# RiskChemi_Monitor_V1_04M1.net
KiCad netlist of a schematic drawn in Altium Designer
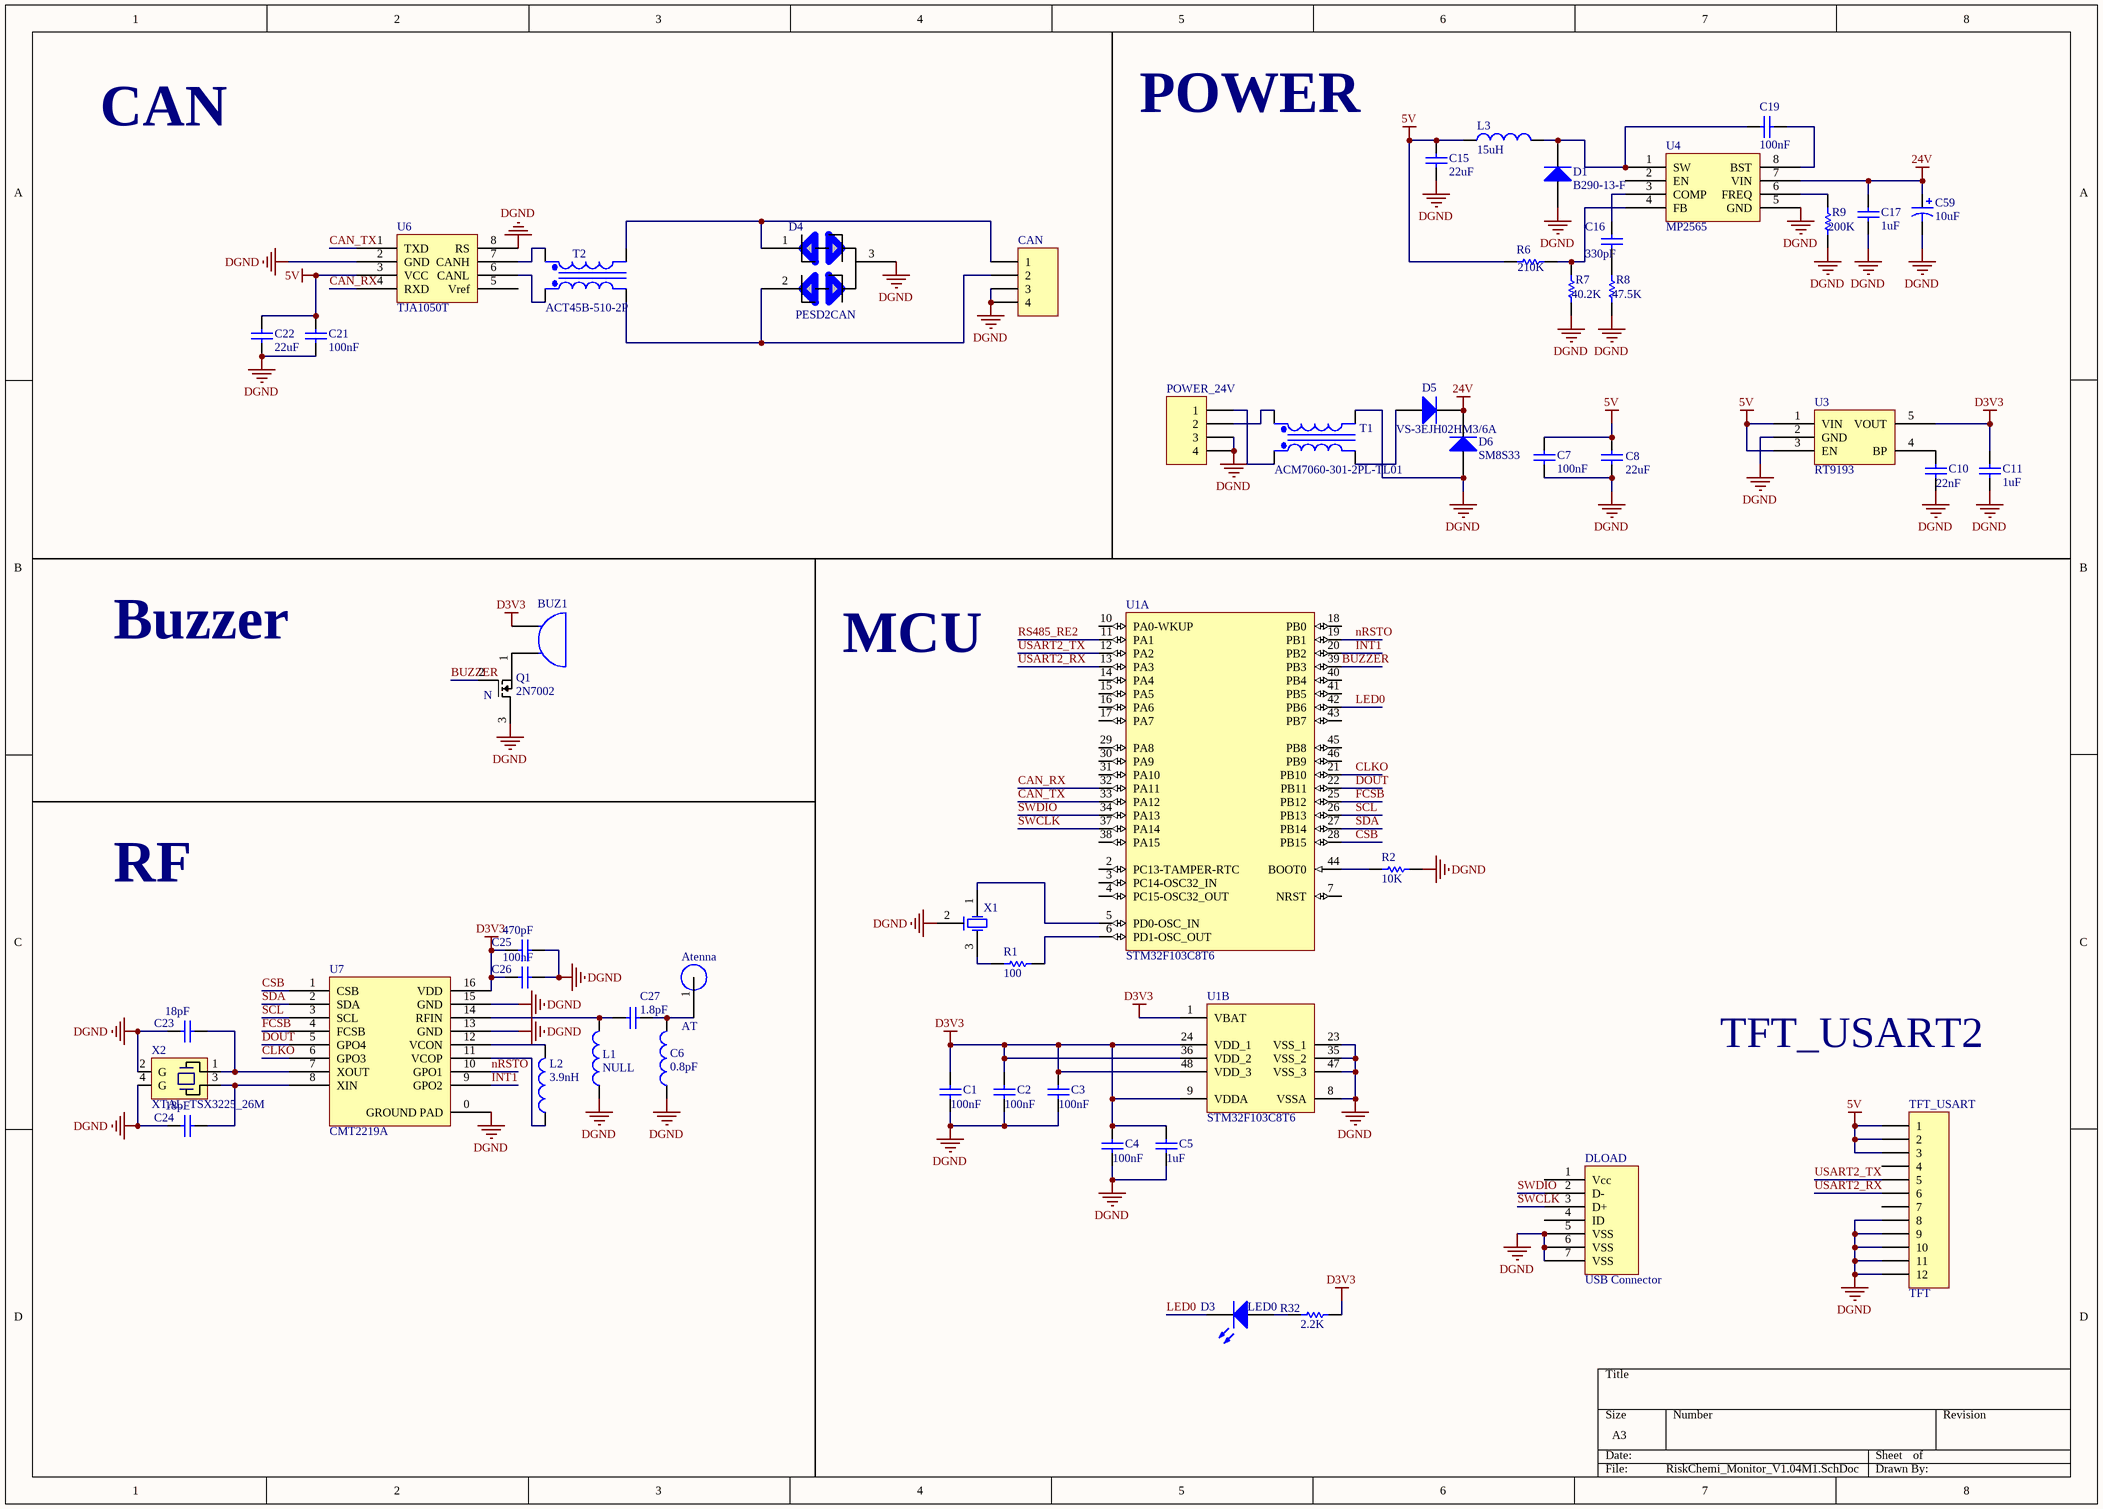
[diagram p0: RiskChemi_Monitor_V1.04M1.SchDoc]

(export (version "E")
  (design (tool "Eeschema 10.0.6"))
  (components
    (comp (ref "Atenna") (value "AT") (footprint "433MHz Atenna") (libsource (lib "MySchlib1") (part "AT")))
    (comp (ref "BUZ1")
      (value "BUZZER")
      (footprint "BUZ0905")
      (description "Buzzer")
      (libsource (lib "杂元件库") (part "BUZZER"))
    )
    (comp (ref "C1")
      (value "100nF")
      (footprint "0603")
      (description "Capacitor")
      (fields (field (name "PUBLISHER") "Altium Limited"))
      (libsource (lib "Miscellaneous Devices") (part "Cap"))
    )
    (comp (ref "C2")
      (value "100nF")
      (footprint "0603")
      (description "Capacitor")
      (fields (field (name "PUBLISHER") "Altium Limited"))
      (libsource (lib "Miscellaneous Devices") (part "Cap"))
    )
    (comp (ref "C3")
      (value "100nF")
      (footprint "0603")
      (description "Capacitor")
      (fields (field (name "PUBLISHER") "Altium Limited"))
      (libsource (lib "Miscellaneous Devices") (part "Cap"))
    )
    (comp (ref "C4")
      (value "100nF")
      (footprint "0603")
      (description "Capacitor")
      (fields (field (name "PUBLISHER") "Altium Limited"))
      (libsource (lib "Miscellaneous Devices") (part "Cap"))
    )
    (comp (ref "C5")
      (value "1uF")
      (footprint "0603")
      (description "Capacitor")
      (fields (field (name "PUBLISHER") "Altium Limited"))
      (libsource (lib "Miscellaneous Devices") (part "Cap"))
    )
    (comp (ref "C6")
      (value "0.8pF")
      (footprint "Miscellaneous Devices:0402")
      (description "Inductor")
      (fields (field (name "PUBLISHER") "Altium Limited"))
      (libsource (lib "Miscellaneous Devices") (part "Inductor"))
    )
    (comp (ref "C7")
      (value "100nF")
      (footprint "0805")
      (description "Capacitor,100V")
      (fields (field (name "PUBLISHER") "Altium Limited"))
      (libsource (lib "Miscellaneous Devices") (part "Cap"))
    )
    (comp (ref "C8")
      (value "22uF")
      (footprint "0805")
      (description "Capacitor")
      (fields (field (name "PUBLISHER") "Altium Limited"))
      (libsource (lib "Miscellaneous Devices") (part "Cap"))
    )
    (comp (ref "C10")
      (value "22nF")
      (footprint "BinFeng:0603")
      (description "Capacitor")
      (fields (field (name "PUBLISHER") "Altium Limited"))
      (libsource (lib "Miscellaneous Devices") (part "Cap"))
    )
    (comp (ref "C11")
      (value "1uF")
      (footprint "BinFeng:0603")
      (description "Capacitor")
      (fields (field (name "PUBLISHER") "Altium Limited"))
      (libsource (lib "Miscellaneous Devices") (part "Cap"))
    )
    (comp (ref "C15")
      (value "22uF")
      (footprint "0805")
      (description "Capacitor,50V")
      (fields (field (name "PUBLISHER") "Altium Limited"))
      (libsource (lib "Miscellaneous Devices") (part "Cap"))
    )
    (comp (ref "C16")
      (value "330pF")
      (footprint "BinFeng:0402")
      (description "Capacitor")
      (fields (field (name "PUBLISHER") "Altium Limited"))
      (libsource (lib "Miscellaneous Devices") (part "Cap"))
    )
    (comp (ref "C17")
      (value "1uF")
      (footprint "0805")
      (description "Capacitor,100V")
      (fields (field (name "PUBLISHER") "Altium Limited"))
      (libsource (lib "Miscellaneous Devices") (part "Cap"))
    )
    (comp (ref "C19")
      (value "100nF")
      (footprint "BinFeng:0402")
      (description "Capacitor")
      (fields (field (name "PUBLISHER") "Altium Limited"))
      (libsource (lib "Miscellaneous Devices") (part "Cap"))
    )
    (comp (ref "C21")
      (value "100nF")
      (footprint "0603")
      (description "Capacitor")
      (fields (field (name "PUBLISHER") "Altium Limited"))
      (libsource (lib "Miscellaneous Devices") (part "Cap"))
    )
    (comp (ref "C22")
      (value "22uF")
      (footprint "0805")
      (description "Capacitor")
      (fields (field (name "PUBLISHER") "Altium Limited"))
      (libsource (lib "Miscellaneous Devices") (part "Cap"))
    )
    (comp (ref "C23")
      (value "18pF")
      (footprint "BinFeng:0402")
      (description "Capacitor")
      (fields (field (name "PUBLISHER") "Altium Limited"))
      (libsource (lib "Miscellaneous Devices") (part "Cap"))
    )
    (comp (ref "C24")
      (value "18pF")
      (footprint "BinFeng:0402")
      (description "Capacitor")
      (fields (field (name "PUBLISHER") "Altium Limited"))
      (libsource (lib "Miscellaneous Devices") (part "Cap"))
    )
    (comp (ref "C25")
      (value "470pF")
      (footprint "BinFeng:0402")
      (description "Capacitor")
      (fields (field (name "PUBLISHER") "Altium Limited"))
      (libsource (lib "Miscellaneous Devices") (part "Cap"))
    )
    (comp (ref "C26")
      (value "100nF")
      (footprint "BinFeng:0603")
      (description "Capacitor")
      (fields (field (name "PUBLISHER") "Altium Limited"))
      (libsource (lib "Miscellaneous Devices") (part "Cap"))
    )
    (comp (ref "C27")
      (value "1.8pF")
      (footprint "BinFeng:nosilk_0402")
      (description "Capacitor")
      (fields (field (name "PUBLISHER") "Altium Limited"))
      (libsource (lib "Miscellaneous Devices") (part "Cap"))
    )
    (comp (ref "C59")
      (value "10uF")
      (footprint "6032_pol")
      (description "Polarized Capacitor (Radial)")
      (fields (field (name "PUBLISHER") "Altium Limited"))
      (libsource (lib "Miscellaneous Devices") (part "Cap Pol1"))
    )
    (comp (ref "CAN")
      (value "Header 4")
      (footprint "C3000VS")
      (description "Header, 4-Pin")
      (fields (field (name "PUBLISHER") "Altium Limited"))
      (libsource (lib "") (part "Header 4_1"))
    )
    (comp (ref "D1")
      (value "B290-13-F")
      (footprint "back:B290")
      (description "Default Diode")
      (fields (field (name "PUBLISHER") "Altium Limited"))
      (libsource (lib "Miscellaneous Devices") (part "Diode"))
    )
    (comp (ref "D3")
      (value "LED0")
      (footprint "LED")
      (description "green LED")
      (fields (field (name "PUBLISHER") "Altium Limited"))
      (libsource (lib "Miscellaneous Devices") (part "LED0"))
    )
    (comp (ref "D4")
      (value "PESD2CAN")
      (footprint "SOT23")
      (libsource (lib "BinFeng_Connectors") (part "PESD1CAN"))
    )
    (comp (ref "D5")
      (value "VS-3EJH02HM3/6A")
      (footprint "back:B290")
      (description "1 Amp General Purpose Rectifier")
      (fields (field (name "PUBLISHER") "Altium Limited"))
      (libsource (lib "Miscellaneous Devices") (part "Diode 1N4007"))
    )
    (comp (ref "D6")
      (value "SM8S33")
      (footprint "SM8S")
      (description "1 Amp General Purpose Rectifier")
      (fields (field (name "PUBLISHER") "Altium Limited"))
      (libsource (lib "Miscellaneous Devices") (part "Diode 1N4007"))
    )
    (comp (ref "DLOAD")
      (value "USB Connector")
      (footprint "Mini_USB")
      (libsource (lib "BinFeng_Connectors") (part "Component_1"))
    )
    (comp (ref "L1")
      (value "NULL")
      (footprint "Miscellaneous Devices:0402")
      (description "Inductor")
      (fields (field (name "PUBLISHER") "Altium Limited"))
      (libsource (lib "Miscellaneous Devices") (part "Inductor"))
    )
    (comp (ref "L2")
      (value "3.9nH")
      (footprint "BinFeng:0603")
      (description "Inductor")
      (fields (field (name "PUBLISHER") "Altium Limited"))
      (libsource (lib "Miscellaneous Devices") (part "Inductor"))
    )
    (comp (ref "L3")
      (value "15uH")
      (footprint "4*4 Inductor")
      (description "Inductor, 1A")
      (fields (field (name "PUBLISHER") "Altium Limited"))
      (libsource (lib "Miscellaneous Devices") (part "Inductor"))
    )
    (comp (ref "POWER_24V")
      (value "Header 4")
      (footprint "C3000VS")
      (description "Header, 4-Pin")
      (fields (field (name "PUBLISHER") "Altium Limited"))
      (libsource (lib "Miscellaneous Connectors") (part "Header 4"))
    )
    (comp (ref "Q1") (value "2N7002") (footprint "2N7002") (libsource (lib "seeder") (part "N-MOSFET")))
    (comp (ref "R1")
      (value "100")
      (footprint "back:0603")
      (description "Resistor")
      (fields (field (name "PUBLISHER") "Altium Limited"))
      (libsource (lib "Miscellaneous Devices") (part "Res1"))
    )
    (comp (ref "R2")
      (value "10K")
      (footprint "back:0603")
      (description "Resistor")
      (fields (field (name "PUBLISHER") "Altium Limited"))
      (libsource (lib "Miscellaneous Devices") (part "Res1"))
    )
    (comp (ref "R6")
      (value "210K")
      (footprint "BinFeng:0402")
      (description "Resistor")
      (fields (field (name "PUBLISHER") "Altium Limited"))
      (libsource (lib "Miscellaneous Devices") (part "Res1"))
    )
    (comp (ref "R7")
      (value "40.2K")
      (footprint "BinFeng:0402")
      (description "Resistor")
      (fields (field (name "PUBLISHER") "Altium Limited"))
      (libsource (lib "Miscellaneous Devices") (part "Res1"))
    )
    (comp (ref "R8")
      (value "47.5K")
      (footprint "BinFeng:0402")
      (description "Resistor")
      (fields (field (name "PUBLISHER") "Altium Limited"))
      (libsource (lib "Miscellaneous Devices") (part "Res1"))
    )
    (comp (ref "R9")
      (value "200K")
      (footprint "BinFeng:0402")
      (description "Resistor")
      (fields (field (name "PUBLISHER") "Altium Limited"))
      (libsource (lib "Miscellaneous Devices") (part "Res1"))
    )
    (comp (ref "R32")
      (value "2.2K")
      (footprint "BinFeng:0603")
      (description "Resistor")
      (fields (field (name "PUBLISHER") "Altium Limited"))
      (libsource (lib "Miscellaneous Devices") (part "Res1"))
    )
    (comp (ref "T1")
      (value "ACM7060-301-2PL-TL01")
      (footprint "ACM7060-301-2P-TL01")
      (description "Transformer (Equivalent Circuit Model)")
      (fields (field (name "PUBLISHER") "Altium Limited"))
      (libsource (lib "Miscellaneous Devices") (part "Trans Eq"))
    )
    (comp (ref "T2")
      (value "ACT45B-510-2P")
      (footprint "ACT45B-510-2P")
      (description "Transformer (Equivalent Circuit Model)")
      (fields (field (name "PUBLISHER") "Altium Limited"))
      (libsource (lib "Miscellaneous Devices") (part "Trans Eq"))
    )
    (comp (ref "TFT_USART")
      (value "TFT")
      (footprint "FCC_10pin_1mm")
      (description "Header, 12-Pin")
      (fields (field (name "PUBLISHER") "Altium Limited"))
      (libsource (lib "Miscellaneous Connectors") (part "Header 12"))
    )
    (comp (ref "U1")
      (value "STM32F103C8T6")
      (footprint "STM-LQFP48_N")
      (libsource (lib "STMicroelectronics STM32 F1") (part "STM32F103C8T6"))
    )
    (comp (ref "U3") (value "RT9193") (footprint "SOT-23-5") (libsource (lib "BinFeng_IC") (part "RT9193")))
    (comp (ref "U4")
      (value "MP2565")
      (footprint "SO8")
      (description "DCDC 4.5V~28V input 1.8V ~5V output low power")
      (libsource (lib "BinFeng_IC") (part "MP1584"))
    )
    (comp (ref "U6")
      (value "TJA1050T")
      (footprint "SO8")
      (description "CAN Tranceiver")
      (libsource (lib "BinFeng_IC") (part "TJA1050T"))
    )
    (comp (ref "U7")
      (value "CMT2219A")
      (footprint "back:QFN16")
      (libsource (lib "BinFeng_IC") (part "CMT2219A"))
    )
    (comp (ref "X1") (value "8M smd") (footprint "8Mhz_XTAL") (libsource (lib "Schlib1") (part "8M smd")))
    (comp (ref "X2")
      (value "XTAL_TSX3225_26M")
      (footprint "XTAL3225")
      (libsource (lib "BinFeng_IC") (part "XTAL_Negative"))
    )
  )
  (nets
    (net (code "1") (name "/BUZZER") (class "Default")
      (node (ref "Q1") (pin "2") (pinfunction "G_2") (pintype "passive"))
      (node (ref "U1") (pin "39") (pinfunction "PB3_39") (pintype "bidirectional"))
    )
    (net (code "2") (name "/CAN_RX") (class "Default")
      (node (ref "U1") (pin "32") (pinfunction "PA11_32") (pintype "bidirectional"))
      (node (ref "U6") (pin "4") (pinfunction "RXD_4") (pintype "passive"))
    )
    (net (code "3") (name "/CAN_TX") (class "Default")
      (node (ref "U1") (pin "33") (pinfunction "PA12_33") (pintype "bidirectional"))
      (node (ref "U6") (pin "1") (pinfunction "TXD_1") (pintype "passive"))
    )
    (net (code "4") (name "/CLKO") (class "Default")
      (node (ref "U1") (pin "21") (pinfunction "PB10_21") (pintype "bidirectional"))
      (node (ref "U7") (pin "6") (pinfunction "GPO3_6") (pintype "passive"))
    )
    (net (code "5") (name "/CSB") (class "Default")
      (node (ref "U1") (pin "28") (pinfunction "PB15_28") (pintype "bidirectional"))
      (node (ref "U7") (pin "1") (pinfunction "CSB_1") (pintype "passive"))
    )
    (net (code "6") (name "/DOUT") (class "Default")
      (node (ref "U1") (pin "22") (pinfunction "PB11_22") (pintype "bidirectional"))
      (node (ref "U7") (pin "5") (pinfunction "GPO4_5") (pintype "passive"))
    )
    (net (code "7") (name "/FCSB") (class "Default")
      (node (ref "U1") (pin "25") (pinfunction "PB12_25") (pintype "bidirectional"))
      (node (ref "U7") (pin "4") (pinfunction "FCSB_4") (pintype "passive"))
    )
    (net (code "8") (name "/INT1") (class "Default")
      (node (ref "U1") (pin "20") (pinfunction "PB2_20") (pintype "bidirectional"))
      (node (ref "U7") (pin "9") (pinfunction "GPO2_9") (pintype "passive"))
    )
    (net (code "9") (name "/LED0") (class "Default")
      (node (ref "D3") (pin "2") (pinfunction "K_2") (pintype "passive"))
      (node (ref "U1") (pin "42") (pinfunction "PB6_42") (pintype "bidirectional"))
    )
    (net (code "10") (name "/RS485_RE2") (class "Default")
      (node (ref "U1") (pin "11") (pinfunction "PA1_11") (pintype "bidirectional"))
    )
    (net (code "11") (name "/SCL") (class "Default")
      (node (ref "U1") (pin "26") (pinfunction "PB13_26") (pintype "bidirectional"))
      (node (ref "U7") (pin "3") (pinfunction "SCL_3") (pintype "passive"))
    )
    (net (code "12") (name "/SDA") (class "Default")
      (node (ref "U1") (pin "27") (pinfunction "PB14_27") (pintype "bidirectional"))
      (node (ref "U7") (pin "2") (pinfunction "SDA_2") (pintype "passive"))
    )
    (net (code "13") (name "/SWCLK") (class "Default")
      (node (ref "DLOAD") (pin "3") (pinfunction "D+_3") (pintype "passive"))
      (node (ref "U1") (pin "37") (pinfunction "PA14_37") (pintype "bidirectional"))
    )
    (net (code "14") (name "/SWDIO") (class "Default")
      (node (ref "DLOAD") (pin "2") (pinfunction "D-_2") (pintype "passive"))
      (node (ref "U1") (pin "34") (pinfunction "PA13_34") (pintype "bidirectional"))
    )
    (net (code "15") (name "/USART2_RX") (class "Default")
      (node (ref "TFT_USART") (pin "6") (pinfunction "6_6") (pintype "passive"))
      (node (ref "U1") (pin "13") (pinfunction "PA3_13") (pintype "bidirectional"))
    )
    (net (code "16") (name "/USART2_TX") (class "Default")
      (node (ref "TFT_USART") (pin "5") (pinfunction "5_5") (pintype "passive"))
      (node (ref "U1") (pin "12") (pinfunction "PA2_12") (pintype "bidirectional"))
    )
    (net (code "17") (name "/nRSTO") (class "Default")
      (node (ref "U1") (pin "19") (pinfunction "PB1_19") (pintype "bidirectional"))
      (node (ref "U7") (pin "10") (pinfunction "GPO1_10") (pintype "passive"))
    )
    (net (code "18") (name "5V") (class "Default")
      (node (ref "C15") (pin "2") (pinfunction "2_2") (pintype "passive"))
      (node (ref "C21") (pin "1") (pinfunction "1_1") (pintype "passive"))
      (node (ref "C22") (pin "2") (pinfunction "2_2") (pintype "passive"))
      (node (ref "C7") (pin "2") (pinfunction "2_2") (pintype "passive"))
      (node (ref "C8") (pin "2") (pinfunction "2_2") (pintype "passive"))
      (node (ref "L3") (pin "1") (pinfunction "1_1") (pintype "passive"))
      (node (ref "R6") (pin "2") (pinfunction "2_2") (pintype "passive"))
      (node (ref "TFT_USART") (pin "1") (pinfunction "1_1") (pintype "passive"))
      (node (ref "TFT_USART") (pin "2") (pinfunction "2_2") (pintype "passive"))
      (node (ref "TFT_USART") (pin "3") (pinfunction "3_3") (pintype "passive"))
      (node (ref "U3") (pin "1") (pinfunction "VIN_1") (pintype "passive"))
      (node (ref "U3") (pin "3") (pinfunction "EN_3") (pintype "passive"))
      (node (ref "U6") (pin "3") (pinfunction "VCC_3") (pintype "passive"))
    )
    (net (code "19") (name "24V") (class "Default")
      (node (ref "C17") (pin "2") (pinfunction "2_2") (pintype "passive"))
      (node (ref "C59") (pin "1") (pinfunction "1_1") (pintype "passive"))
      (node (ref "D5") (pin "2") (pinfunction "K_2") (pintype "passive"))
      (node (ref "D6") (pin "2") (pinfunction "K_2") (pintype "passive"))
      (node (ref "U4") (pin "7") (pinfunction "VIN_7") (pintype "passive"))
    )
    (net (code "20") (name "D3V3") (class "Default")
      (node (ref "BUZ1") (pin "1") (pinfunction "A_1") (pintype "passive"))
      (node (ref "C1") (pin "2") (pinfunction "2_2") (pintype "passive"))
      (node (ref "C11") (pin "2") (pinfunction "2_2") (pintype "passive"))
      (node (ref "C2") (pin "2") (pinfunction "2_2") (pintype "passive"))
      (node (ref "C25") (pin "2") (pinfunction "2_2") (pintype "passive"))
      (node (ref "C26") (pin "2") (pinfunction "2_2") (pintype "passive"))
      (node (ref "C3") (pin "2") (pinfunction "2_2") (pintype "passive"))
      (node (ref "C4") (pin "2") (pinfunction "2_2") (pintype "passive"))
      (node (ref "C5") (pin "2") (pinfunction "2_2") (pintype "passive"))
      (node (ref "R32") (pin "1") (pinfunction "1_1") (pintype "passive"))
      (node (ref "U1") (pin "1") (pinfunction "VBAT_1") (pintype "power_in"))
      (node (ref "U1") (pin "24") (pinfunction "VDD_1_24") (pintype "power_in"))
      (node (ref "U1") (pin "36") (pinfunction "VDD_2_36") (pintype "power_in"))
      (node (ref "U1") (pin "48") (pinfunction "VDD_3_48") (pintype "power_in"))
      (node (ref "U1") (pin "9") (pinfunction "VDDA_9") (pintype "power_in"))
      (node (ref "U3") (pin "5") (pinfunction "VOUT_5") (pintype "passive"))
      (node (ref "U7") (pin "16") (pinfunction "VDD_16") (pintype "passive"))
    )
    (net (code "21") (name "DGND") (class "Default")
      (node (ref "C1") (pin "1") (pinfunction "1_1") (pintype "passive"))
      (node (ref "C10") (pin "1") (pinfunction "1_1") (pintype "passive"))
      (node (ref "C11") (pin "1") (pinfunction "1_1") (pintype "passive"))
      (node (ref "C15") (pin "1") (pinfunction "1_1") (pintype "passive"))
      (node (ref "C17") (pin "1") (pinfunction "1_1") (pintype "passive"))
      (node (ref "C2") (pin "1") (pinfunction "1_1") (pintype "passive"))
      (node (ref "C21") (pin "2") (pinfunction "2_2") (pintype "passive"))
      (node (ref "C22") (pin "1") (pinfunction "1_1") (pintype "passive"))
      (node (ref "C23") (pin "2") (pinfunction "2_2") (pintype "passive"))
      (node (ref "C24") (pin "2") (pinfunction "2_2") (pintype "passive"))
      (node (ref "C25") (pin "1") (pinfunction "1_1") (pintype "passive"))
      (node (ref "C26") (pin "1") (pinfunction "1_1") (pintype "passive"))
      (node (ref "C3") (pin "1") (pinfunction "1_1") (pintype "passive"))
      (node (ref "C4") (pin "1") (pinfunction "1_1") (pintype "passive"))
      (node (ref "C5") (pin "1") (pinfunction "1_1") (pintype "passive"))
      (node (ref "C59") (pin "2") (pinfunction "2_2") (pintype "passive"))
      (node (ref "C6") (pin "1") (pinfunction "1_1") (pintype "passive"))
      (node (ref "C7") (pin "1") (pinfunction "1_1") (pintype "passive"))
      (node (ref "C8") (pin "1") (pinfunction "1_1") (pintype "passive"))
      (node (ref "CAN") (pin "3") (pinfunction "3_3") (pintype "passive"))
      (node (ref "CAN") (pin "4") (pinfunction "4_4") (pintype "passive"))
      (node (ref "D1") (pin "1") (pinfunction "A_1") (pintype "passive"))
      (node (ref "D4") (pin "3") (pinfunction "13_3") (pintype "passive"))
      (node (ref "D6") (pin "1") (pinfunction "A_1") (pintype "passive"))
      (node (ref "DLOAD") (pin "5") (pinfunction "VSS_5") (pintype "passive"))
      (node (ref "DLOAD") (pin "6") (pinfunction "VSS_6") (pintype "passive"))
      (node (ref "DLOAD") (pin "7") (pinfunction "VSS_7") (pintype "passive"))
      (node (ref "L1") (pin "1") (pinfunction "1_1") (pintype "passive"))
      (node (ref "POWER_24V") (pin "3") (pinfunction "3_3") (pintype "passive"))
      (node (ref "POWER_24V") (pin "4") (pinfunction "4_4") (pintype "passive"))
      (node (ref "Q1") (pin "3") (pinfunction "S_3") (pintype "passive"))
      (node (ref "R2") (pin "2") (pinfunction "2_2") (pintype "passive"))
      (node (ref "R7") (pin "1") (pinfunction "1_1") (pintype "passive"))
      (node (ref "R8") (pin "1") (pinfunction "1_1") (pintype "passive"))
      (node (ref "R9") (pin "1") (pinfunction "1_1") (pintype "passive"))
      (node (ref "T1") (pin "4") (pinfunction "Sec-_4") (pintype "passive"))
      (node (ref "TFT_USART") (pin "10") (pinfunction "10_10") (pintype "passive"))
      (node (ref "TFT_USART") (pin "11") (pinfunction "11_11") (pintype "passive"))
      (node (ref "TFT_USART") (pin "12") (pinfunction "12_12") (pintype "passive"))
      (node (ref "TFT_USART") (pin "8") (pinfunction "8_8") (pintype "passive"))
      (node (ref "TFT_USART") (pin "9") (pinfunction "9_9") (pintype "passive"))
      (node (ref "U1") (pin "23") (pinfunction "VSS_1_23") (pintype "power_in"))
      (node (ref "U1") (pin "35") (pinfunction "VSS_2_35") (pintype "power_in"))
      (node (ref "U1") (pin "47") (pinfunction "VSS_3_47") (pintype "power_in"))
      (node (ref "U1") (pin "8") (pinfunction "VSSA_8") (pintype "power_in"))
      (node (ref "U3") (pin "2") (pinfunction "GND_2") (pintype "passive"))
      (node (ref "U4") (pin "5") (pinfunction "GND_5") (pintype "passive"))
      (node (ref "U6") (pin "2") (pinfunction "GND_2") (pintype "passive"))
      (node (ref "U6") (pin "8") (pinfunction "RS_8") (pintype "passive"))
      (node (ref "U7") (pin "0") (pinfunction "GROUND_PAD_0") (pintype "passive"))
      (node (ref "U7") (pin "13") (pinfunction "GND_13") (pintype "passive"))
      (node (ref "U7") (pin "15") (pinfunction "GND_15") (pintype "passive"))
      (node (ref "X1") (pin "2") (pinfunction "GND_2") (pintype "passive"))
      (node (ref "X2") (pin "2") (pinfunction "G_2") (pintype "passive"))
      (node (ref "X2") (pin "4") (pinfunction "G_4") (pintype "passive"))
    )
    (net (code "22") (name "Net-(Atenna-Pad1)") (class "Default")
      (node (ref "Atenna") (pin "1") (pinfunction "1_1") (pintype "passive"))
      (node (ref "C27") (pin "1") (pinfunction "1_1") (pintype "passive"))
      (node (ref "C6") (pin "2") (pinfunction "2_2") (pintype "passive"))
    )
    (net (code "23") (name "Net-(BUZ1-B)") (class "Default")
      (node (ref "BUZ1") (pin "2") (pinfunction "B_2") (pintype "passive"))
      (node (ref "Q1") (pin "1") (pinfunction "D_1") (pintype "passive"))
    )
    (net (code "24") (name "Net-(C16-Pad2)") (class "Default")
      (node (ref "C16") (pin "2") (pinfunction "2_2") (pintype "passive"))
      (node (ref "R8") (pin "2") (pinfunction "2_2") (pintype "passive"))
    )
    (net (code "25") (name "Net-(D1-K)") (class "Default")
      (node (ref "C19") (pin "2") (pinfunction "2_2") (pintype "passive"))
      (node (ref "D1") (pin "2") (pinfunction "K_2") (pintype "passive"))
      (node (ref "L3") (pin "2") (pinfunction "2_2") (pintype "passive"))
      (node (ref "U4") (pin "1") (pinfunction "SW_1") (pintype "passive"))
    )
    (net (code "26") (name "Net-(D3-A)") (class "Default")
      (node (ref "D3") (pin "1") (pinfunction "A_1") (pintype "passive"))
      (node (ref "R32") (pin "2") (pinfunction "2_2") (pintype "passive"))
    )
    (net (code "27") (name "Net-(D4-11)") (class "Default")
      (node (ref "CAN") (pin "1") (pinfunction "1_1") (pintype "passive"))
      (node (ref "D4") (pin "1") (pinfunction "11_1") (pintype "passive"))
      (node (ref "T2") (pin "4") (pinfunction "Sec-_4") (pintype "passive"))
    )
    (net (code "28") (name "Net-(D4-12)") (class "Default")
      (node (ref "CAN") (pin "2") (pinfunction "2_2") (pintype "passive"))
      (node (ref "D4") (pin "2") (pinfunction "12_2") (pintype "passive"))
      (node (ref "T2") (pin "2") (pinfunction "Pri-_2") (pintype "passive"))
    )
    (net (code "29") (name "Net-(D5-A)") (class "Default")
      (node (ref "D5") (pin "1") (pinfunction "A_1") (pintype "passive"))
      (node (ref "T1") (pin "2") (pinfunction "Pri-_2") (pintype "passive"))
    )
    (net (code "30") (name "Net-(T1-Pri+)") (class "Default")
      (node (ref "POWER_24V") (pin "1") (pinfunction "1_1") (pintype "passive"))
      (node (ref "T1") (pin "1") (pinfunction "Pri+_1") (pintype "passive"))
    )
    (net (code "31") (name "Net-(T1-Sec+)") (class "Default")
      (node (ref "POWER_24V") (pin "2") (pinfunction "2_2") (pintype "passive"))
      (node (ref "T1") (pin "3") (pinfunction "Sec+_3") (pintype "passive"))
    )
    (net (code "32") (name "Net-(T2-Pri+)") (class "Default")
      (node (ref "T2") (pin "1") (pinfunction "Pri+_1") (pintype "passive"))
      (node (ref "U6") (pin "6") (pinfunction "CANL_6") (pintype "passive"))
    )
    (net (code "33") (name "Net-(T2-Sec+)") (class "Default")
      (node (ref "T2") (pin "3") (pinfunction "Sec+_3") (pintype "passive"))
      (node (ref "U6") (pin "7") (pinfunction "CANH_7") (pintype "passive"))
    )
    (net (code "34") (name "Net-(U1A-BOOT0)") (class "Default")
      (node (ref "R2") (pin "1") (pinfunction "1_1") (pintype "passive"))
      (node (ref "U1") (pin "44") (pinfunction "BOOT0_44") (pintype "input"))
    )
    (net (code "35") (name "Net-(U1A-PD0-OSC_IN)") (class "Default")
      (node (ref "U1") (pin "5") (pinfunction "PD0-OSC_IN_5") (pintype "bidirectional"))
      (node (ref "X1") (pin "1") (pinfunction "OSC1_1") (pintype "passive"))
    )
    (net (code "36") (name "Net-(U1A-PD1-OSC_OUT)") (class "Default")
      (node (ref "R1") (pin "2") (pinfunction "2_2") (pintype "passive"))
      (node (ref "U1") (pin "6") (pinfunction "PD1-OSC_OUT_6") (pintype "bidirectional"))
    )
    (net (code "37") (name "Net-(U3-BP)") (class "Default")
      (node (ref "C10") (pin "2") (pinfunction "2_2") (pintype "passive"))
      (node (ref "U3") (pin "4") (pinfunction "BP_4") (pintype "passive"))
    )
    (net (code "38") (name "Net-(U4-BST)") (class "Default")
      (node (ref "C19") (pin "1") (pinfunction "1_1") (pintype "passive"))
      (node (ref "U4") (pin "8") (pinfunction "BST_8") (pintype "passive"))
    )
    (net (code "39") (name "Net-(U4-COMP)") (class "Default")
      (node (ref "C16") (pin "1") (pinfunction "1_1") (pintype "passive"))
      (node (ref "U4") (pin "3") (pinfunction "COMP_3") (pintype "passive"))
    )
    (net (code "40") (name "Net-(U4-FB)") (class "Default")
      (node (ref "R6") (pin "1") (pinfunction "1_1") (pintype "passive"))
      (node (ref "R7") (pin "2") (pinfunction "2_2") (pintype "passive"))
      (node (ref "U4") (pin "4") (pinfunction "FB_4") (pintype "passive"))
    )
    (net (code "41") (name "Net-(U4-FREQ)") (class "Default")
      (node (ref "R9") (pin "2") (pinfunction "2_2") (pintype "passive"))
      (node (ref "U4") (pin "6") (pinfunction "FREQ_6") (pintype "passive"))
    )
    (net (code "42") (name "Net-(U7-RFIN)") (class "Default")
      (node (ref "C27") (pin "2") (pinfunction "2_2") (pintype "passive"))
      (node (ref "L1") (pin "2") (pinfunction "2_2") (pintype "passive"))
      (node (ref "U7") (pin "14") (pinfunction "RFIN_14") (pintype "passive"))
    )
    (net (code "43") (name "Net-(U7-VCON)") (class "Default")
      (node (ref "L2") (pin "2") (pinfunction "2_2") (pintype "passive"))
      (node (ref "U7") (pin "12") (pinfunction "VCON_12") (pintype "passive"))
    )
    (net (code "44") (name "Net-(U7-VCOP)") (class "Default")
      (node (ref "L2") (pin "1") (pinfunction "1_1") (pintype "passive"))
      (node (ref "U7") (pin "11") (pinfunction "VCOP_11") (pintype "passive"))
    )
    (net (code "45") (name "Net-(U7-XIN)") (class "Default")
      (node (ref "C24") (pin "1") (pinfunction "1_1") (pintype "passive"))
      (node (ref "U7") (pin "8") (pinfunction "XIN_8") (pintype "passive"))
      (node (ref "X2") (pin "3") (pintype "passive"))
    )
    (net (code "46") (name "Net-(U7-XOUT)") (class "Default")
      (node (ref "C23") (pin "1") (pinfunction "1_1") (pintype "passive"))
      (node (ref "U7") (pin "7") (pinfunction "XOUT_7") (pintype "passive"))
      (node (ref "X2") (pin "1") (pintype "passive"))
    )
    (net (code "47") (name "Net-(X1-OSC2)") (class "Default")
      (node (ref "R1") (pin "1") (pinfunction "1_1") (pintype "passive"))
      (node (ref "X1") (pin "3") (pinfunction "OSC2_3") (pintype "passive"))
    )
    (net (code "48") (name "unconnected-(DLOAD-ID-Pad4)") (class "Default")
      (node (ref "DLOAD") (pin "4") (pinfunction "ID_4") (pintype "passive"))
    )
    (net (code "49") (name "unconnected-(DLOAD-Vcc-Pad1)") (class "Default")
      (node (ref "DLOAD") (pin "1") (pinfunction "Vcc_1") (pintype "passive"))
    )
    (net (code "50") (name "unconnected-(TFT_USART-Pad4)") (class "Default")
      (node (ref "TFT_USART") (pin "4") (pinfunction "4_4") (pintype "passive"))
    )
    (net (code "51") (name "unconnected-(TFT_USART-Pad7)") (class "Default")
      (node (ref "TFT_USART") (pin "7") (pinfunction "7_7") (pintype "passive"))
    )
    (net (code "52") (name "unconnected-(U1A-NRST-Pad7)") (class "Default")
      (node (ref "U1") (pin "7") (pinfunction "NRST_7") (pintype "bidirectional"))
    )
    (net (code "53") (name "unconnected-(U1A-PA0-WKUP-Pad10)") (class "Default")
      (node (ref "U1") (pin "10") (pinfunction "PA0-WKUP_10") (pintype "bidirectional"))
    )
    (net (code "54") (name "unconnected-(U1A-PA4-Pad14)") (class "Default")
      (node (ref "U1") (pin "14") (pinfunction "PA4_14") (pintype "bidirectional"))
    )
    (net (code "55") (name "unconnected-(U1A-PA5-Pad15)") (class "Default")
      (node (ref "U1") (pin "15") (pinfunction "PA5_15") (pintype "bidirectional"))
    )
    (net (code "56") (name "unconnected-(U1A-PA6-Pad16)") (class "Default")
      (node (ref "U1") (pin "16") (pinfunction "PA6_16") (pintype "bidirectional"))
    )
    (net (code "57") (name "unconnected-(U1A-PA7-Pad17)") (class "Default")
      (node (ref "U1") (pin "17") (pinfunction "PA7_17") (pintype "bidirectional"))
    )
    (net (code "58") (name "unconnected-(U1A-PA8-Pad29)") (class "Default")
      (node (ref "U1") (pin "29") (pinfunction "PA8_29") (pintype "bidirectional"))
    )
    (net (code "59") (name "unconnected-(U1A-PA9-Pad30)") (class "Default")
      (node (ref "U1") (pin "30") (pinfunction "PA9_30") (pintype "bidirectional"))
    )
    (net (code "60") (name "unconnected-(U1A-PA10-Pad31)") (class "Default")
      (node (ref "U1") (pin "31") (pinfunction "PA10_31") (pintype "bidirectional"))
    )
    (net (code "61") (name "unconnected-(U1A-PA15-Pad38)") (class "Default")
      (node (ref "U1") (pin "38") (pinfunction "PA15_38") (pintype "bidirectional"))
    )
    (net (code "62") (name "unconnected-(U1A-PB0-Pad18)") (class "Default")
      (node (ref "U1") (pin "18") (pinfunction "PB0_18") (pintype "bidirectional"))
    )
    (net (code "63") (name "unconnected-(U1A-PB4-Pad40)") (class "Default")
      (node (ref "U1") (pin "40") (pinfunction "PB4_40") (pintype "bidirectional"))
    )
    (net (code "64") (name "unconnected-(U1A-PB5-Pad41)") (class "Default")
      (node (ref "U1") (pin "41") (pinfunction "PB5_41") (pintype "bidirectional"))
    )
    (net (code "65") (name "unconnected-(U1A-PB7-Pad43)") (class "Default")
      (node (ref "U1") (pin "43") (pinfunction "PB7_43") (pintype "bidirectional"))
    )
    (net (code "66") (name "unconnected-(U1A-PB8-Pad45)") (class "Default")
      (node (ref "U1") (pin "45") (pinfunction "PB8_45") (pintype "bidirectional"))
    )
    (net (code "67") (name "unconnected-(U1A-PB9-Pad46)") (class "Default")
      (node (ref "U1") (pin "46") (pinfunction "PB9_46") (pintype "bidirectional"))
    )
    (net (code "68") (name "unconnected-(U1A-PC13-TAMPER-RTC-Pad2)") (class "Default")
      (node (ref "U1") (pin "2") (pinfunction "PC13-TAMPER-RTC_2") (pintype "bidirectional"))
    )
    (net (code "69") (name "unconnected-(U1A-PC14-OSC32_IN-Pad3)") (class "Default")
      (node (ref "U1") (pin "3") (pinfunction "PC14-OSC32_IN_3") (pintype "bidirectional"))
    )
    (net (code "70") (name "unconnected-(U1A-PC15-OSC32_OUT-Pad4)") (class "Default")
      (node (ref "U1") (pin "4") (pinfunction "PC15-OSC32_OUT_4") (pintype "bidirectional"))
    )
    (net (code "71") (name "unconnected-(U4-EN-Pad2)") (class "Default")
      (node (ref "U4") (pin "2") (pinfunction "EN_2") (pintype "passive"))
    )
    (net (code "72") (name "unconnected-(U6-Vref-Pad5)") (class "Default")
      (node (ref "U6") (pin "5") (pinfunction "Vref_5") (pintype "passive"))
    )
  )
)
